# Controller_Sheet.net
KiCad netlist of a schematic drawn in Altium Designer
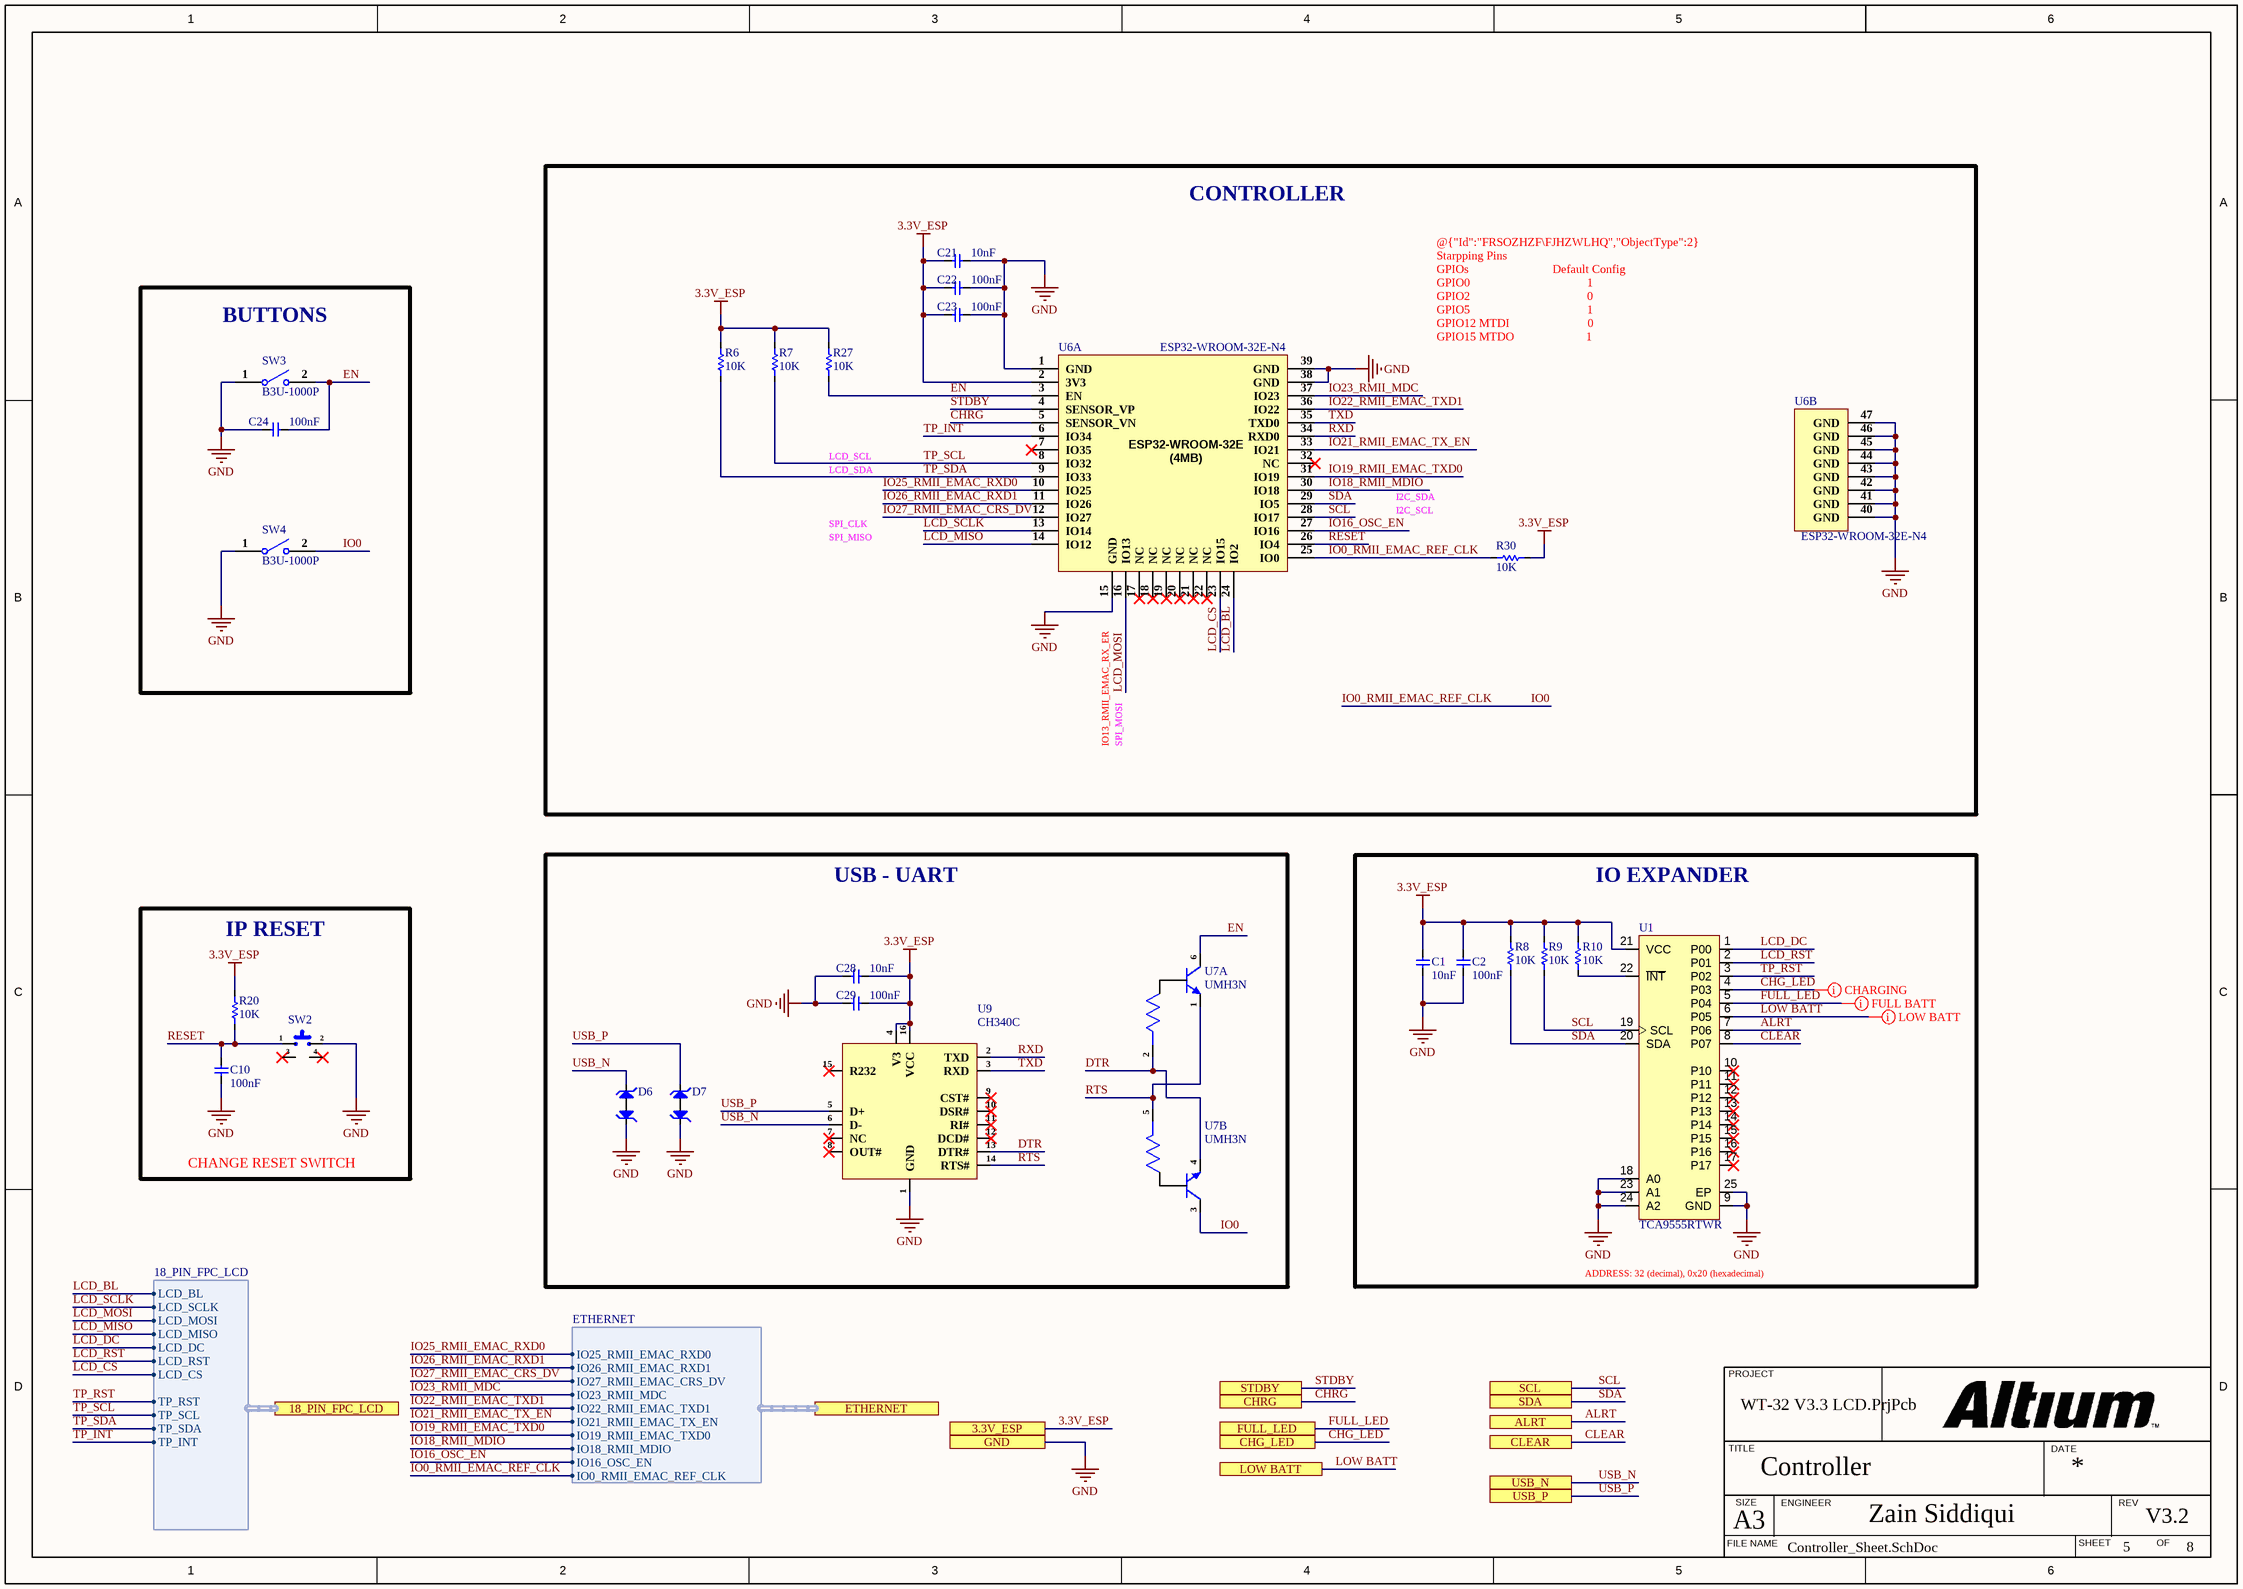
[diagram p0: Controller_Sheet.SchDoc]

(export (version "E")
  (design (tool "Eeschema 10.0.6"))
  (components
    (comp (ref "C1")
      (value "10nF")
      (footprint "Cap-0402")
      (description "CAP CER 10000PF 25V X7R 0402")
      (fields
        (field (name "MANUFACTURER") "Yageo")
        (field (name "MANUFACTURER PART NUMBER") "CC0402KRX7R8BB103")
      )
      (libsource (lib "eSpark Libraries") (part "CC0402KRX7R8BB103"))
    )
    (comp (ref "C2")
      (value "100nF")
      (footprint "cap-0402")
      (description "CAP CER 0.1UF 50V X7R 0402")
      (fields
        (field (name "MANUFACTURER") "TDK")
        (field (name "MANUFACTURER PART NUMBER") "C1005X7R1H104KT000F")
      )
      (libsource (lib "eSpark Libraries") (part "C1005X7R1H104KT000F"))
    )
    (comp (ref "C10")
      (value "100nF")
      (footprint "cap-0402")
      (description "CAP CER 0.1UF 50V X7R 0402")
      (fields
        (field (name "MANUFACTURER") "TDK")
        (field (name "MANUFACTURER PART NUMBER") "C1005X7R1H104KT000F")
      )
      (libsource (lib "eSpark Libraries") (part "C1005X7R1H104KT000F"))
    )
    (comp (ref "C21")
      (value "10nF")
      (footprint "Cap-0402")
      (description "CAP CER 10000PF 25V X7R 0402")
      (fields
        (field (name "MANUFACTURER") "Yageo")
        (field (name "MANUFACTURER PART NUMBER") "CC0402KRX7R8BB103")
      )
      (libsource (lib "eSpark Libraries") (part "CC0402KRX7R8BB103"))
    )
    (comp (ref "C22")
      (value "100nF")
      (footprint "cap-0402")
      (description "CAP CER 0.1UF 50V X7R 0402")
      (fields
        (field (name "MANUFACTURER") "TDK")
        (field (name "MANUFACTURER PART NUMBER") "C1005X7R1H104KT000F")
      )
      (libsource (lib "eSpark Libraries") (part "C1005X7R1H104KT000F"))
    )
    (comp (ref "C23")
      (value "100nF")
      (footprint "cap-0402")
      (description "CAP CER 0.1UF 50V X7R 0402")
      (fields
        (field (name "MANUFACTURER") "TDK")
        (field (name "MANUFACTURER PART NUMBER") "C1005X7R1H104KT000F")
      )
      (libsource (lib "eSpark Libraries") (part "C1005X7R1H104KT000F"))
    )
    (comp (ref "C24")
      (value "100nF")
      (footprint "cap-0402")
      (description "CAP CER 0.1UF 50V X7R 0402")
      (fields
        (field (name "MANUFACTURER") "TDK")
        (field (name "MANUFACTURER PART NUMBER") "C1005X7R1H104KT000F")
      )
      (libsource (lib "eSpark Libraries") (part "C1005X7R1H104KT000F"))
    )
    (comp (ref "C28")
      (value "10nF")
      (footprint "Cap-0402")
      (description "CAP CER 10000PF 25V X7R 0402")
      (fields
        (field (name "MANUFACTURER") "Yageo")
        (field (name "MANUFACTURER PART NUMBER") "CC0402KRX7R8BB103")
      )
      (libsource (lib "eSpark Libraries") (part "CC0402KRX7R8BB103"))
    )
    (comp (ref "C29")
      (value "100nF")
      (footprint "cap-0402")
      (description "CAP CER 0.1UF 50V X7R 0402")
      (fields
        (field (name "MANUFACTURER") "TDK")
        (field (name "MANUFACTURER PART NUMBER") "C1005X7R1H104KT000F")
      )
      (libsource (lib "eSpark Libraries") (part "C1005X7R1H104KT000F"))
    )
    (comp (ref "D6")
      (value "PESD5V0H1BSFYL")
      (footprint "DSN0603-2")
      (description "TVS DIODE 5VWM 6.3VC DSN0603-2")
      (fields (field (name "MANUFACTURER") "Nexperia") (field (name "LCSC PART NUMBER") "C477989"))
      (libsource (lib "eSpark Libraries") (part "PESD5V0H1BSFYL"))
    )
    (comp (ref "D7")
      (value "PESD5V0H1BSFYL")
      (footprint "DSN0603-2")
      (description "TVS DIODE 5VWM 6.3VC DSN0603-2")
      (fields (field (name "MANUFACTURER") "Nexperia") (field (name "LCSC PART NUMBER") "C477989"))
      (libsource (lib "eSpark Libraries") (part "PESD5V0H1BSFYL"))
    )
    (comp (ref "R6")
      (value "10K")
      (footprint "Res-0402")
      (description "RES 10K OHM 1% 1/16W 0402")
      (fields
        (field (name "MANUFACTURER") "Yageo")
        (field (name "MANUFACTURER PART NUMBER") "RC0402FR-0710KL")
      )
      (libsource (lib "eSpark Libraries") (part "RC0402FR-0710KL"))
    )
    (comp (ref "R7")
      (value "10K")
      (footprint "Res-0402")
      (description "RES 10K OHM 1% 1/16W 0402")
      (fields
        (field (name "MANUFACTURER") "Yageo")
        (field (name "MANUFACTURER PART NUMBER") "RC0402FR-0710KL")
      )
      (libsource (lib "eSpark Libraries") (part "RC0402FR-0710KL"))
    )
    (comp (ref "R8")
      (value "10K")
      (footprint "Res-0402")
      (description "RES 10K OHM 1% 1/16W 0402")
      (fields
        (field (name "MANUFACTURER") "Yageo")
        (field (name "MANUFACTURER PART NUMBER") "RC0402FR-0710KL")
      )
      (libsource (lib "eSpark Libraries") (part "RC0402FR-0710KL"))
    )
    (comp (ref "R9")
      (value "10K")
      (footprint "Res-0402")
      (description "RES 10K OHM 1% 1/16W 0402")
      (fields
        (field (name "MANUFACTURER") "Yageo")
        (field (name "MANUFACTURER PART NUMBER") "RC0402FR-0710KL")
      )
      (libsource (lib "eSpark Libraries") (part "RC0402FR-0710KL"))
    )
    (comp (ref "R10")
      (value "10K")
      (footprint "Res-0402")
      (description "RES 10K OHM 1% 1/16W 0402")
      (fields
        (field (name "MANUFACTURER") "Yageo")
        (field (name "MANUFACTURER PART NUMBER") "RC0402FR-0710KL")
      )
      (libsource (lib "eSpark Libraries") (part "RC0402FR-0710KL"))
    )
    (comp (ref "R20")
      (value "10K")
      (footprint "Res-0402")
      (description "RES 10K OHM 1% 1/16W 0402")
      (fields
        (field (name "MANUFACTURER") "Yageo")
        (field (name "MANUFACTURER PART NUMBER") "RC0402FR-0710KL")
      )
      (libsource (lib "eSpark Libraries") (part "RC0402FR-0710KL"))
    )
    (comp (ref "R27")
      (value "10K")
      (footprint "Res-0402")
      (description "RES 10K OHM 1% 1/16W 0402")
      (fields
        (field (name "MANUFACTURER") "Yageo")
        (field (name "MANUFACTURER PART NUMBER") "RC0402FR-0710KL")
      )
      (libsource (lib "eSpark Libraries") (part "RC0402FR-0710KL"))
    )
    (comp (ref "R30")
      (value "10K")
      (footprint "Res-0402")
      (description "RES 10K OHM 1% 1/16W 0402")
      (fields
        (field (name "MANUFACTURER") "Yageo")
        (field (name "MANUFACTURER PART NUMBER") "RC0402FR-0710KL")
      )
      (libsource (lib "eSpark Libraries") (part "RC0402FR-0710KL"))
    )
    (comp (ref "SW2")
      (value "TC-6615-9.5-260G")
      (footprint "TC-6615-9.5-260G")
      (description "Tactile Switch SPST 260gf 9.5mm 6mm x 6mm Through Hole, Right Angle")
      (fields (field (name "MANUFACTURER") "HCTL") (field (name "LCSC PART NUMBER") "C2845278"))
      (libsource (lib "eSpark Libraries") (part "TC-6615-9.5-260G"))
    )
    (comp (ref "SW3")
      (value "B3U-1000P")
      (footprint "B3U-1000P")
      (description "SWITCH TACTILE SPST-NO 0.05A 12V")
      (fields (field (name "MANUFACTURER") "Omron") (field (name "LCSC PART NUMBER") "C231329"))
      (libsource (lib "eSpark Libraries") (part "B3U-1000P"))
    )
    (comp (ref "SW4")
      (value "B3U-1000P")
      (footprint "B3U-1000P")
      (description "SWITCH TACTILE SPST-NO 0.05A 12V")
      (fields (field (name "MANUFACTURER") "Omron") (field (name "LCSC PART NUMBER") "C231329"))
      (libsource (lib "eSpark Libraries") (part "B3U-1000P"))
    )
    (comp (ref "U1")
      (value "TCA9555RTWR")
      (footprint "WQFN-24-EP(4x4)")
      (fields (field (name "MANUFACTURER") "Texas Instruments") (field (name "LCSC PART NUMBER") "C140277"))
      (libsource (lib "eSpark Libraries") (part "TCA9555RTWR"))
    )
    (comp (ref "U6")
      (value "ESP32-WROOM-32E-N4")
      (footprint "38-SMD Module")
      (description "RX TXRX MOD WIFI TRACE ANT SMD")
      (fields (field (name "MANUFACTURER") "Espressif Systems") (field (name "LCSC PART NUMBER") "C701341"))
      (libsource (lib "eSpark Libraries") (part "ESP32-WROOM-32E-N4"))
    )
    (comp (ref "U7")
      (value "UMH3N")
      (footprint "SC-70-6_")
      (description "2 NPN pre-biased (Dual) 150mW 100mA 50V SC-70-6(SOT-363) Digital Transistors ROHS")
      (fields (field (name "MANUFACTURER") "Changjiang") (field (name "LCSC PART NUMBER") "C62892"))
      (libsource (lib "eSpark Libraries") (part "UMH3N"))
    )
    (comp (ref "U9")
      (value "CH340C")
      (footprint "SOP-16")
      (description "2Mbps Transceiver USB 2.0 SOP-16 USB ICs ROHS")
      (fields (field (name "MANUFACTURER") "WCH") (field (name "LCSC PART NUMBER") "C84681"))
      (libsource (lib "eSpark Libraries") (part "CH340C"))
    )
  )
  (nets
    (net (code "3") (name "/ALRT") (class "Default")
      (node (ref "U1") (pin "7") (pinfunction "P06_7") (pintype "passive"))
    )
    (net (code "4") (name "/CHG_LED") (class "Default")
      (node (ref "U1") (pin "4") (pinfunction "P03_4") (pintype "passive"))
    )
    (net (code "5") (name "/CHRG") (class "Default")
      (node (ref "U6") (pin "5") (pinfunction "SENSOR_VN_5") (pintype "passive"))
    )
    (net (code "6") (name "/CLEAR") (class "Default")
      (node (ref "U1") (pin "8") (pinfunction "P07_8") (pintype "passive"))
    )
    (net (code "7") (name "/DTR") (class "Default")
      (node (ref "U7") (pin "2") (pintype "passive"))
      (node (ref "U7") (pin "4") (pinfunction "E_4") (pintype "passive"))
      (node (ref "U9") (pin "13") (pinfunction "DTR#_13") (pintype "passive"))
    )
    (net (code "8") (name "/EN") (class "Default")
      (node (ref "C24") (pin "1") (pinfunction "1_1") (pintype "passive"))
      (node (ref "R27") (pin "1") (pinfunction "1_1") (pintype "passive"))
      (node (ref "SW3") (pin "2") (pinfunction "2_2") (pintype "passive"))
      (node (ref "U6") (pin "3") (pinfunction "EN_3") (pintype "passive"))
      (node (ref "U7") (pin "6") (pinfunction "C_6") (pintype "passive"))
    )
    (net (code "9") (name "/FULL_LED") (class "Default")
      (node (ref "U1") (pin "5") (pinfunction "P04_5") (pintype "passive"))
    )
    (net (code "10") (name "/IO0") (class "Default")
      (node (ref "R30") (pin "1") (pinfunction "1_1") (pintype "passive"))
      (node (ref "SW4") (pin "2") (pinfunction "2_2") (pintype "passive"))
      (node (ref "U6") (pin "25") (pinfunction "IO0_25") (pintype "passive"))
      (node (ref "U7") (pin "3") (pinfunction "C_3") (pintype "passive"))
    )
    (net (code "11") (name "/IO16_OSC_EN") (class "Default")
      (node (ref "U6") (pin "27") (pinfunction "IO16_27") (pintype "passive"))
    )
    (net (code "12") (name "/IO18_RMII_MDIO") (class "Default")
      (node (ref "U6") (pin "30") (pinfunction "IO18_30") (pintype "passive"))
    )
    (net (code "13") (name "/IO19_RMII_EMAC_TXD0") (class "Default")
      (node (ref "U6") (pin "31") (pinfunction "IO19_31") (pintype "passive"))
    )
    (net (code "14") (name "/IO21_RMII_EMAC_TX_EN") (class "Default")
      (node (ref "U6") (pin "33") (pinfunction "IO21_33") (pintype "passive"))
    )
    (net (code "15") (name "/IO22_RMII_EMAC_TXD1") (class "Default")
      (node (ref "U6") (pin "36") (pinfunction "IO22_36") (pintype "passive"))
    )
    (net (code "16") (name "/IO23_RMII_MDC") (class "Default")
      (node (ref "U6") (pin "37") (pinfunction "IO23_37") (pintype "passive"))
    )
    (net (code "17") (name "/IO25_RMII_EMAC_RXD0") (class "Default")
      (node (ref "U6") (pin "10") (pinfunction "IO25_10") (pintype "passive"))
    )
    (net (code "18") (name "/IO26_RMII_EMAC_RXD1") (class "Default")
      (node (ref "U6") (pin "11") (pinfunction "IO26_11") (pintype "passive"))
    )
    (net (code "19") (name "/IO27_RMII_EMAC_CRS_DV") (class "Default")
      (node (ref "U6") (pin "12") (pinfunction "IO27_12") (pintype "passive"))
    )
    (net (code "20") (name "/LCD_BL") (class "Default")
      (node (ref "U6") (pin "24") (pinfunction "IO2_24") (pintype "passive"))
    )
    (net (code "21") (name "/LCD_CS") (class "Default")
      (node (ref "U6") (pin "23") (pinfunction "IO15_23") (pintype "passive"))
    )
    (net (code "22") (name "/LCD_DC") (class "Default")
      (node (ref "U1") (pin "1") (pinfunction "P00_1") (pintype "passive"))
    )
    (net (code "23") (name "/LCD_MISO") (class "Default")
      (node (ref "U6") (pin "14") (pinfunction "IO12_14") (pintype "passive"))
    )
    (net (code "24") (name "/LCD_MOSI") (class "Default")
      (node (ref "U6") (pin "16") (pinfunction "IO13_16") (pintype "passive"))
    )
    (net (code "25") (name "/LCD_RST") (class "Default")
      (node (ref "U1") (pin "2") (pinfunction "P01_2") (pintype "passive"))
    )
    (net (code "26") (name "/LCD_SCLK") (class "Default")
      (node (ref "U6") (pin "13") (pinfunction "IO14_13") (pintype "passive"))
    )
    (net (code "27") (name "/LOW BATT") (class "Default")
      (node (ref "U1") (pin "6") (pinfunction "P05_6") (pintype "passive"))
    )
    (net (code "28") (name "/RESET") (class "Default")
      (node (ref "C10") (pin "1") (pinfunction "1_1") (pintype "passive"))
      (node (ref "R20") (pin "1") (pinfunction "1_1") (pintype "passive"))
      (node (ref "SW2") (pin "1") (pinfunction "1_1") (pintype "passive"))
      (node (ref "U6") (pin "26") (pinfunction "IO4_26") (pintype "passive"))
    )
    (net (code "29") (name "/RTS") (class "Default")
      (node (ref "U7") (pin "1") (pinfunction "E_1") (pintype "passive"))
      (node (ref "U7") (pin "5") (pintype "passive"))
      (node (ref "U9") (pin "14") (pinfunction "RTS#_14") (pintype "passive"))
    )
    (net (code "30") (name "/RXD") (class "Default")
      (node (ref "U6") (pin "34") (pinfunction "RXD0_34") (pintype "passive"))
      (node (ref "U9") (pin "2") (pinfunction "TXD_2") (pintype "passive"))
    )
    (net (code "31") (name "/SCL") (class "Default")
      (node (ref "R9") (pin "1") (pinfunction "1_1") (pintype "passive"))
      (node (ref "U1") (pin "19") (pinfunction "SCL_19") (pintype "passive"))
      (node (ref "U6") (pin "28") (pinfunction "IO17_28") (pintype "passive"))
    )
    (net (code "32") (name "/SDA") (class "Default")
      (node (ref "R8") (pin "1") (pinfunction "1_1") (pintype "passive"))
      (node (ref "U1") (pin "20") (pinfunction "SDA_20") (pintype "passive"))
      (node (ref "U6") (pin "29") (pinfunction "IO5_29") (pintype "passive"))
    )
    (net (code "33") (name "/STDBY") (class "Default")
      (node (ref "U6") (pin "4") (pinfunction "SENSOR_VP_4") (pintype "passive"))
    )
    (net (code "34") (name "/TP_INT") (class "Default")
      (node (ref "U6") (pin "6") (pinfunction "IO34_6") (pintype "passive"))
    )
    (net (code "35") (name "/TP_RST") (class "Default")
      (node (ref "U1") (pin "3") (pinfunction "P02_3") (pintype "passive"))
    )
    (net (code "36") (name "/TP_SCL") (class "Default")
      (node (ref "R7") (pin "1") (pinfunction "1_1") (pintype "passive"))
      (node (ref "U6") (pin "8") (pinfunction "IO32_8") (pintype "passive"))
    )
    (net (code "37") (name "/TP_SDA") (class "Default")
      (node (ref "R6") (pin "1") (pinfunction "1_1") (pintype "passive"))
      (node (ref "U6") (pin "9") (pinfunction "IO33_9") (pintype "passive"))
    )
    (net (code "38") (name "/TXD") (class "Default")
      (node (ref "U6") (pin "35") (pinfunction "TXD0_35") (pintype "passive"))
      (node (ref "U9") (pin "3") (pinfunction "RXD_3") (pintype "passive"))
    )
    (net (code "39") (name "/USB_N") (class "Default")
      (node (ref "D6") (pin "2") (pinfunction "2_2") (pintype "passive"))
      (node (ref "U9") (pin "6") (pinfunction "D-_6") (pintype "passive"))
    )
    (net (code "40") (name "/USB_P") (class "Default")
      (node (ref "D7") (pin "2") (pinfunction "2_2") (pintype "passive"))
      (node (ref "U9") (pin "5") (pinfunction "D+_5") (pintype "passive"))
    )
    (net (code "43") (name "3.3V_ESP") (class "Default")
      (node (ref "C1") (pin "1") (pinfunction "1_1") (pintype "passive"))
      (node (ref "C2") (pin "1") (pinfunction "1_1") (pintype "passive"))
      (node (ref "C21") (pin "2") (pinfunction "2_2") (pintype "passive"))
      (node (ref "C22") (pin "2") (pinfunction "2_2") (pintype "passive"))
      (node (ref "C23") (pin "2") (pinfunction "2_2") (pintype "passive"))
      (node (ref "C28") (pin "1") (pinfunction "1_1") (pintype "passive"))
      (node (ref "C29") (pin "1") (pinfunction "1_1") (pintype "passive"))
      (node (ref "R10") (pin "2") (pinfunction "2_2") (pintype "passive"))
      (node (ref "R20") (pin "2") (pinfunction "2_2") (pintype "passive"))
      (node (ref "R27") (pin "2") (pinfunction "2_2") (pintype "passive"))
      (node (ref "R30") (pin "2") (pinfunction "2_2") (pintype "passive"))
      (node (ref "R6") (pin "2") (pinfunction "2_2") (pintype "passive"))
      (node (ref "R7") (pin "2") (pinfunction "2_2") (pintype "passive"))
      (node (ref "R8") (pin "2") (pinfunction "2_2") (pintype "passive"))
      (node (ref "R9") (pin "2") (pinfunction "2_2") (pintype "passive"))
      (node (ref "U1") (pin "21") (pinfunction "VCC_21") (pintype "passive"))
      (node (ref "U6") (pin "2") (pinfunction "3V3_2") (pintype "passive"))
      (node (ref "U9") (pin "16") (pinfunction "VCC_16") (pintype "passive"))
      (node (ref "U9") (pin "4") (pinfunction "V3_4") (pintype "passive"))
    )
    (net (code "44") (name "GND") (class "Default")
      (node (ref "C1") (pin "2") (pinfunction "2_2") (pintype "passive"))
      (node (ref "C10") (pin "2") (pinfunction "2_2") (pintype "passive"))
      (node (ref "C2") (pin "2") (pinfunction "2_2") (pintype "passive"))
      (node (ref "C21") (pin "1") (pinfunction "1_1") (pintype "passive"))
      (node (ref "C22") (pin "1") (pinfunction "1_1") (pintype "passive"))
      (node (ref "C23") (pin "1") (pinfunction "1_1") (pintype "passive"))
      (node (ref "C24") (pin "2") (pinfunction "2_2") (pintype "passive"))
      (node (ref "C28") (pin "2") (pinfunction "2_2") (pintype "passive"))
      (node (ref "C29") (pin "2") (pinfunction "2_2") (pintype "passive"))
      (node (ref "D6") (pin "1") (pinfunction "1_1") (pintype "passive"))
      (node (ref "D7") (pin "1") (pinfunction "1_1") (pintype "passive"))
      (node (ref "SW2") (pin "2") (pinfunction "2_2") (pintype "passive"))
      (node (ref "SW3") (pin "1") (pinfunction "1_1") (pintype "passive"))
      (node (ref "SW4") (pin "1") (pinfunction "1_1") (pintype "passive"))
      (node (ref "U1") (pin "18") (pinfunction "A0_18") (pintype "passive"))
      (node (ref "U1") (pin "23") (pinfunction "A1_23") (pintype "passive"))
      (node (ref "U1") (pin "24") (pinfunction "A2_24") (pintype "passive"))
      (node (ref "U1") (pin "25") (pinfunction "EP_25") (pintype "passive"))
      (node (ref "U1") (pin "9") (pinfunction "GND_9") (pintype "passive"))
      (node (ref "U6") (pin "1") (pinfunction "GND_1") (pintype "passive"))
      (node (ref "U6") (pin "15") (pinfunction "GND_15") (pintype "passive"))
      (node (ref "U6") (pin "38") (pinfunction "GND_38") (pintype "passive"))
      (node (ref "U6") (pin "39") (pinfunction "GND_39") (pintype "passive"))
      (node (ref "U6") (pin "40") (pinfunction "GND_40") (pintype "passive"))
      (node (ref "U6") (pin "41") (pinfunction "GND_41") (pintype "passive"))
      (node (ref "U6") (pin "42") (pinfunction "GND_42") (pintype "passive"))
      (node (ref "U6") (pin "43") (pinfunction "GND_43") (pintype "passive"))
      (node (ref "U6") (pin "44") (pinfunction "GND_44") (pintype "passive"))
      (node (ref "U6") (pin "45") (pinfunction "GND_45") (pintype "passive"))
      (node (ref "U6") (pin "46") (pinfunction "GND_46") (pintype "passive"))
      (node (ref "U6") (pin "47") (pinfunction "GND_47") (pintype "passive"))
      (node (ref "U9") (pin "1") (pinfunction "GND_1") (pintype "passive"))
    )
    (net (code "45") (name "Net-(U1-~{INT})") (class "Default")
      (node (ref "R10") (pin "1") (pinfunction "1_1") (pintype "passive"))
      (node (ref "U1") (pin "22") (pinfunction "~{INT}_22") (pintype "passive"))
    )
    (net (code "46") (name "unconnected-(SW2-Pad3)") (class "Default")
      (node (ref "SW2") (pin "3") (pinfunction "3_3") (pintype "passive+no_connect"))
    )
    (net (code "47") (name "unconnected-(SW2-Pad4)") (class "Default")
      (node (ref "SW2") (pin "4") (pinfunction "4_4") (pintype "passive+no_connect"))
    )
    (net (code "48") (name "unconnected-(U1-P10-Pad10)") (class "Default")
      (node (ref "U1") (pin "10") (pinfunction "P10_10") (pintype "passive+no_connect"))
    )
    (net (code "49") (name "unconnected-(U1-P11-Pad11)") (class "Default")
      (node (ref "U1") (pin "11") (pinfunction "P11_11") (pintype "passive+no_connect"))
    )
    (net (code "50") (name "unconnected-(U1-P12-Pad12)") (class "Default")
      (node (ref "U1") (pin "12") (pinfunction "P12_12") (pintype "passive+no_connect"))
    )
    (net (code "51") (name "unconnected-(U1-P13-Pad13)") (class "Default")
      (node (ref "U1") (pin "13") (pinfunction "P13_13") (pintype "passive+no_connect"))
    )
    (net (code "52") (name "unconnected-(U1-P14-Pad14)") (class "Default")
      (node (ref "U1") (pin "14") (pinfunction "P14_14") (pintype "passive+no_connect"))
    )
    (net (code "53") (name "unconnected-(U1-P15-Pad15)") (class "Default")
      (node (ref "U1") (pin "15") (pinfunction "P15_15") (pintype "passive+no_connect"))
    )
    (net (code "54") (name "unconnected-(U1-P16-Pad16)") (class "Default")
      (node (ref "U1") (pin "16") (pinfunction "P16_16") (pintype "passive+no_connect"))
    )
    (net (code "55") (name "unconnected-(U1-P17-Pad17)") (class "Default")
      (node (ref "U1") (pin "17") (pinfunction "P17_17") (pintype "passive+no_connect"))
    )
    (net (code "56") (name "unconnected-(U6A-IO35-Pad7)") (class "Default")
      (node (ref "U6") (pin "7") (pinfunction "IO35_7") (pintype "passive+no_connect"))
    )
    (net (code "57") (name "unconnected-(U6A-NC-Pad17)") (class "Default")
      (node (ref "U6") (pin "17") (pinfunction "NC_17") (pintype "passive+no_connect"))
    )
    (net (code "58") (name "unconnected-(U6A-NC-Pad18)") (class "Default")
      (node (ref "U6") (pin "18") (pinfunction "NC_18") (pintype "passive+no_connect"))
    )
    (net (code "59") (name "unconnected-(U6A-NC-Pad19)") (class "Default")
      (node (ref "U6") (pin "19") (pinfunction "NC_19") (pintype "passive+no_connect"))
    )
    (net (code "60") (name "unconnected-(U6A-NC-Pad20)") (class "Default")
      (node (ref "U6") (pin "20") (pinfunction "NC_20") (pintype "passive+no_connect"))
    )
    (net (code "61") (name "unconnected-(U6A-NC-Pad21)") (class "Default")
      (node (ref "U6") (pin "21") (pinfunction "NC_21") (pintype "passive+no_connect"))
    )
    (net (code "62") (name "unconnected-(U6A-NC-Pad22)") (class "Default")
      (node (ref "U6") (pin "22") (pinfunction "NC_22") (pintype "passive+no_connect"))
    )
    (net (code "63") (name "unconnected-(U6A-NC-Pad32)") (class "Default")
      (node (ref "U6") (pin "32") (pinfunction "NC_32") (pintype "passive+no_connect"))
    )
    (net (code "64") (name "unconnected-(U9-CST#-Pad9)") (class "Default")
      (node (ref "U9") (pin "9") (pinfunction "CST#_9") (pintype "passive+no_connect"))
    )
    (net (code "65") (name "unconnected-(U9-DCD#-Pad12)") (class "Default")
      (node (ref "U9") (pin "12") (pinfunction "DCD#_12") (pintype "passive+no_connect"))
    )
    (net (code "66") (name "unconnected-(U9-DSR#-Pad10)") (class "Default")
      (node (ref "U9") (pin "10") (pinfunction "DSR#_10") (pintype "passive+no_connect"))
    )
    (net (code "67") (name "unconnected-(U9-NC-Pad7)") (class "Default")
      (node (ref "U9") (pin "7") (pinfunction "NC_7") (pintype "passive+no_connect"))
    )
    (net (code "68") (name "unconnected-(U9-OUT#-Pad8)") (class "Default")
      (node (ref "U9") (pin "8") (pinfunction "OUT#_8") (pintype "passive+no_connect"))
    )
    (net (code "69") (name "unconnected-(U9-R232-Pad15)") (class "Default")
      (node (ref "U9") (pin "15") (pinfunction "R232_15") (pintype "passive+no_connect"))
    )
    (net (code "70") (name "unconnected-(U9-RI#-Pad11)") (class "Default")
      (node (ref "U9") (pin "11") (pinfunction "RI#_11") (pintype "passive+no_connect"))
    )
  )
)
